# Battery_Charging.net
KiCad netlist of a schematic drawn in Altium Designer
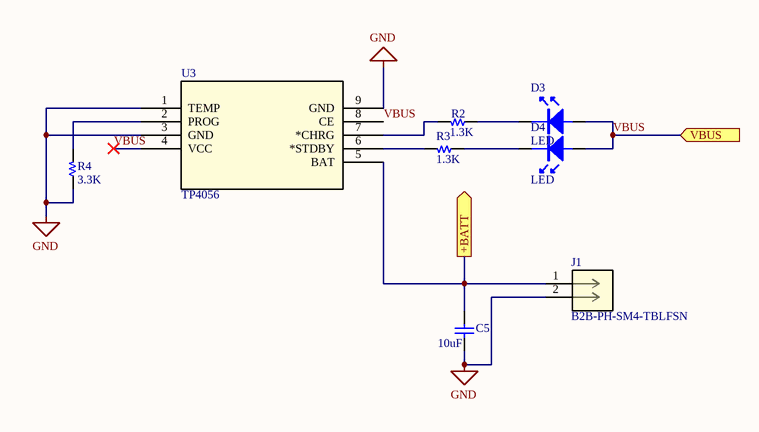
[diagram p0: Battery Charging.SchDoc]

(export (version "E")
  (design (tool "Eeschema 10.0.6"))
  (components
    (comp (ref "C5")
      (value "10uF")
      (footprint "C 0805")
      (description "Capacitor non-pol")
      (libsource (lib "chipfc_libs") (part "Capacitor NP"))
    )
    (comp (ref "D3") (value "LED") (footprint "CAP10UF") (libsource (lib "Devzone_SCHLib") (part "LED")))
    (comp (ref "D4") (value "LED") (footprint "CAP10UF") (libsource (lib "Devzone_SCHLib") (part "LED")))
    (comp (ref "J1")
      (value "B2B-PH-SM4-TBLFSN")
      (footprint "CONN_B2B-PH-SM4-TBLFSN_JST")
      (description "No Description Available")
      (libsource (lib "B2B-PH-SM4-TBLFSN") (part "B2B-PH-SM4-TBLFSN"))
    )
    (comp (ref "R2")
      (value "1.3K")
      (footprint "R 0805")
      (description "Resistor")
      (libsource (lib "chipfc_libs") (part "Resistor"))
    )
    (comp (ref "R3")
      (value "1.3K")
      (footprint "R 0805")
      (description "Resistor")
      (libsource (lib "chipfc_libs") (part "Resistor"))
    )
    (comp (ref "R4")
      (value "3.3K")
      (footprint "R 0805")
      (description "Resistor")
      (libsource (lib "chipfc_libs") (part "Resistor"))
    )
    (comp (ref "U3")
      (value "TP4056")
      (footprint "ESOP8_TPW")
      (description "No Description Available")
      (libsource (lib "TP4056") (part "TP4056"))
    )
  )
  (nets
    (net (code "1") (name "/+BATT") (class "Default")
      (node (ref "C5") (pin "1") (pinfunction "1_1") (pintype "passive"))
      (node (ref "J1") (pin "1") (pinfunction "1_1") (pintype "passive"))
      (node (ref "U3") (pin "5") (pinfunction "BAT_5") (pintype "passive"))
    )
    (net (code "2") (name "/VBUS") (class "Default")
      (node (ref "D3") (pin "1") (pinfunction "1_1") (pintype "passive"))
      (node (ref "D4") (pin "1") (pinfunction "1_1") (pintype "passive"))
      (node (ref "U3") (pin "4") (pinfunction "VCC_4") (pintype "power_in"))
      (node (ref "U3") (pin "8") (pinfunction "CE_8") (pintype "passive"))
    )
    (net (code "3") (name "GND") (class "Default")
      (node (ref "C5") (pin "2") (pinfunction "2_2") (pintype "passive"))
      (node (ref "J1") (pin "2") (pinfunction "2_2") (pintype "passive"))
      (node (ref "R4") (pin "1") (pinfunction "1_1") (pintype "passive"))
      (node (ref "U3") (pin "1") (pinfunction "TEMP_1") (pintype "passive"))
      (node (ref "U3") (pin "3") (pinfunction "GND_3") (pintype "power_in"))
      (node (ref "U3") (pin "9") (pinfunction "GND_9") (pintype "power_in"))
    )
    (net (code "4") (name "Net-(D3-Pad2)") (class "Default")
      (node (ref "D3") (pin "2") (pinfunction "2_2") (pintype "passive"))
      (node (ref "R2") (pin "1") (pinfunction "1_1") (pintype "passive"))
    )
    (net (code "5") (name "Net-(D4-Pad2)") (class "Default")
      (node (ref "D4") (pin "2") (pinfunction "2_2") (pintype "passive"))
      (node (ref "R3") (pin "1") (pinfunction "1_1") (pintype "passive"))
    )
    (net (code "6") (name "Net-(U3-*CHRG)") (class "Default")
      (node (ref "R2") (pin "2") (pinfunction "2_2") (pintype "passive"))
      (node (ref "U3") (pin "7") (pinfunction "*CHRG_7") (pintype "passive"))
    )
    (net (code "7") (name "Net-(U3-*STDBY)") (class "Default")
      (node (ref "R3") (pin "2") (pinfunction "2_2") (pintype "passive"))
      (node (ref "U3") (pin "6") (pinfunction "*STDBY_6") (pintype "passive"))
    )
    (net (code "8") (name "Net-(U3-PROG)") (class "Default")
      (node (ref "R4") (pin "2") (pinfunction "2_2") (pintype "passive"))
      (node (ref "U3") (pin "2") (pinfunction "PROG_2") (pintype "passive"))
    )
  )
)
